# Schematics.net
KiCad netlist of a schematic drawn in Altium Designer
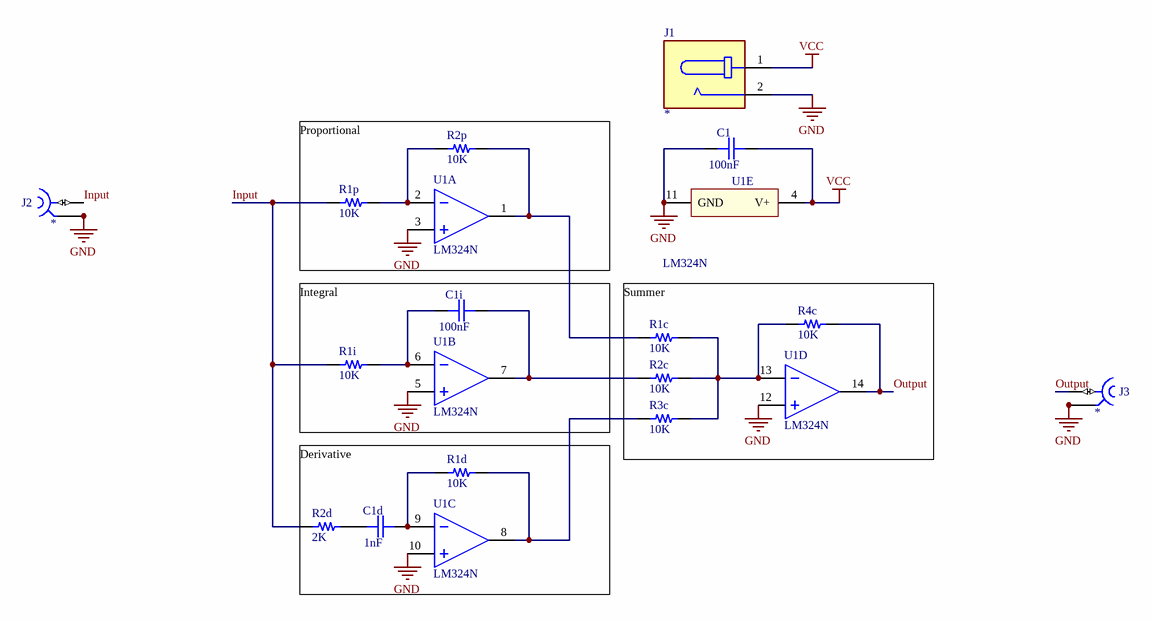
[diagram p0: Schematics.SchDoc]

(export (version "E")
  (design (tool "Eeschema 10.0.6"))
  (components
    (comp (ref "C1")
      (value "100nF")
      (footprint "CAPC4720X215N")
      (description "Non-polarised capacitor")
      (libsource (lib "Schlib") (part "Capacitor"))
    )
    (comp (ref "C1d")
      (value "1nF")
      (footprint "CAPC4720X215N")
      (description "Non-polarised capacitor")
      (libsource (lib "Schlib") (part "Capacitor"))
    )
    (comp (ref "C1i")
      (value "100nF")
      (footprint "CAPC4720X215N")
      (description "Non-polarised capacitor")
      (libsource (lib "Schlib") (part "Capacitor"))
    )
    (comp (ref "J1")
      (value "*")
      (footprint "CUI_PJ-037B")
      (description "2.5 x 6.5 mm, 2.5 A, Horizontal, Through Hole, Dc Power Jack Connector")
      (libsource (lib "Schlib") (part "DC Power Jack Connector"))
    )
    (comp (ref "J2")
      (value "*")
      (footprint "LINX_CONSMA002-L-G")
      (description "SMA Jack 50 Ohm PCB Through Hole")
      (libsource (lib "Schlib") (part "Coax_1Female_1Shield"))
    )
    (comp (ref "J3")
      (value "*")
      (footprint "LINX_CONSMA002-L-G")
      (description "SMA Jack 50 Ohm PCB Through Hole")
      (libsource (lib "") (part "Coax_1Female_1Shield_1"))
    )
    (comp (ref "R1c")
      (value "10K")
      (footprint "RES1016-650X250")
      (description "Resistor")
      (libsource (lib "Schlib") (part "Resistor"))
    )
    (comp (ref "R1d")
      (value "10K")
      (footprint "RES1016-650X250")
      (description "Resistor")
      (libsource (lib "Schlib") (part "Resistor"))
    )
    (comp (ref "R1i")
      (value "10K")
      (footprint "RES1016-650X250")
      (description "Resistor")
      (libsource (lib "Schlib") (part "Resistor"))
    )
    (comp (ref "R1p")
      (value "10K")
      (footprint "RES1016-650X250")
      (description "Resistor")
      (libsource (lib "Schlib") (part "Resistor"))
    )
    (comp (ref "R2c")
      (value "10K")
      (footprint "RES1016-650X250")
      (description "Resistor")
      (libsource (lib "Schlib") (part "Resistor"))
    )
    (comp (ref "R2d")
      (value "2K")
      (footprint "RES1016-650X250")
      (description "Resistor")
      (libsource (lib "Schlib") (part "Resistor"))
    )
    (comp (ref "R2p")
      (value "10K")
      (footprint "RES1016-650X250")
      (description "Resistor")
      (libsource (lib "Schlib") (part "Resistor"))
    )
    (comp (ref "R3c")
      (value "10K")
      (footprint "RES1016-650X250")
      (description "Resistor")
      (libsource (lib "Schlib") (part "Resistor"))
    )
    (comp (ref "R4c")
      (value "10K")
      (footprint "RES1016-650X250")
      (description "Resistor")
      (libsource (lib "Schlib") (part "Resistor"))
    )
    (comp (ref "U1")
      (value "LM324N")
      (footprint "N0014A")
      (description "Low Power Quad Operational Amplifier, 14-pin MDIP")
      (fields (field (name "MANUFACTURER") "Texas Instruments"))
      (libsource (lib "Schlib") (part "LM324N"))
    )
  )
  (nets
    (net (code "1") (name "/Input") (class "Default")
      (node (ref "J2") (pin "1") (pinfunction "1_1") (pintype "bidirectional"))
      (node (ref "R1i") (pin "1") (pinfunction "1_1") (pintype "passive"))
      (node (ref "R1p") (pin "1") (pinfunction "1_1") (pintype "passive"))
      (node (ref "R2d") (pin "1") (pinfunction "1_1") (pintype "passive"))
    )
    (net (code "2") (name "/Output") (class "Default")
      (node (ref "J3") (pin "1") (pinfunction "1_1") (pintype "bidirectional"))
      (node (ref "R4c") (pin "2") (pinfunction "2_2") (pintype "passive"))
      (node (ref "U1") (pin "14") (pinfunction "OUT4_14") (pintype "passive"))
    )
    (net (code "3") (name "GND") (class "Default")
      (node (ref "C1") (pin "1") (pinfunction "1_1") (pintype "passive"))
      (node (ref "J1") (pin "2") (pinfunction "2_2") (pintype "passive"))
      (node (ref "J2") (pin "S1") (pinfunction "2_S1") (pintype "passive"))
      (node (ref "J2") (pin "S2") (pinfunction "2_S2") (pintype "passive"))
      (node (ref "J2") (pin "S3") (pinfunction "2_S3") (pintype "passive"))
      (node (ref "J2") (pin "S4") (pinfunction "2_S4") (pintype "passive"))
      (node (ref "J3") (pin "S1") (pinfunction "2_S1") (pintype "passive"))
      (node (ref "J3") (pin "S2") (pinfunction "2_S2") (pintype "passive"))
      (node (ref "J3") (pin "S3") (pinfunction "2_S3") (pintype "passive"))
      (node (ref "J3") (pin "S4") (pinfunction "2_S4") (pintype "passive"))
      (node (ref "U1") (pin "10") (pinfunction "IN3+_10") (pintype "passive"))
      (node (ref "U1") (pin "11") (pinfunction "GND_11") (pintype "passive"))
      (node (ref "U1") (pin "12") (pinfunction "IN4+_12") (pintype "passive"))
      (node (ref "U1") (pin "3") (pinfunction "IN1+_3") (pintype "passive"))
      (node (ref "U1") (pin "5") (pinfunction "IN2+_5") (pintype "passive"))
    )
    (net (code "4") (name "Net-(C1d-Pad1)") (class "Default")
      (node (ref "C1d") (pin "1") (pinfunction "1_1") (pintype "passive"))
      (node (ref "R2d") (pin "2") (pinfunction "2_2") (pintype "passive"))
    )
    (net (code "5") (name "Net-(U1A-IN1-)") (class "Default")
      (node (ref "R1p") (pin "2") (pinfunction "2_2") (pintype "passive"))
      (node (ref "R2p") (pin "1") (pinfunction "1_1") (pintype "passive"))
      (node (ref "U1") (pin "2") (pinfunction "IN1-_2") (pintype "passive"))
    )
    (net (code "6") (name "Net-(U1A-OUT1)") (class "Default")
      (node (ref "R1c") (pin "1") (pinfunction "1_1") (pintype "passive"))
      (node (ref "R2p") (pin "2") (pinfunction "2_2") (pintype "passive"))
      (node (ref "U1") (pin "1") (pinfunction "OUT1_1") (pintype "passive"))
    )
    (net (code "7") (name "Net-(U1B-IN2-)") (class "Default")
      (node (ref "C1i") (pin "1") (pinfunction "1_1") (pintype "passive"))
      (node (ref "R1i") (pin "2") (pinfunction "2_2") (pintype "passive"))
      (node (ref "U1") (pin "6") (pinfunction "IN2-_6") (pintype "passive"))
    )
    (net (code "8") (name "Net-(U1B-OUT2)") (class "Default")
      (node (ref "C1i") (pin "2") (pinfunction "2_2") (pintype "passive"))
      (node (ref "R2c") (pin "1") (pinfunction "1_1") (pintype "passive"))
      (node (ref "U1") (pin "7") (pinfunction "OUT2_7") (pintype "passive"))
    )
    (net (code "9") (name "Net-(U1C-IN3-)") (class "Default")
      (node (ref "C1d") (pin "2") (pinfunction "2_2") (pintype "passive"))
      (node (ref "R1d") (pin "1") (pinfunction "1_1") (pintype "passive"))
      (node (ref "U1") (pin "9") (pinfunction "IN3-_9") (pintype "passive"))
    )
    (net (code "10") (name "Net-(U1C-OUT3)") (class "Default")
      (node (ref "R1d") (pin "2") (pinfunction "2_2") (pintype "passive"))
      (node (ref "R3c") (pin "1") (pinfunction "1_1") (pintype "passive"))
      (node (ref "U1") (pin "8") (pinfunction "OUT3_8") (pintype "passive"))
    )
    (net (code "11") (name "Net-(U1D-IN4-)") (class "Default")
      (node (ref "R1c") (pin "2") (pinfunction "2_2") (pintype "passive"))
      (node (ref "R2c") (pin "2") (pinfunction "2_2") (pintype "passive"))
      (node (ref "R3c") (pin "2") (pinfunction "2_2") (pintype "passive"))
      (node (ref "R4c") (pin "1") (pinfunction "1_1") (pintype "passive"))
      (node (ref "U1") (pin "13") (pinfunction "IN4-_13") (pintype "passive"))
    )
    (net (code "12") (name "VCC") (class "Default")
      (node (ref "C1") (pin "2") (pinfunction "2_2") (pintype "passive"))
      (node (ref "J1") (pin "1") (pinfunction "1_1") (pintype "passive"))
      (node (ref "U1") (pin "4") (pinfunction "V+_4") (pintype "passive"))
    )
  )
)
